# 09_Connectors.net
KiCad netlist of a schematic drawn in Altium Designer
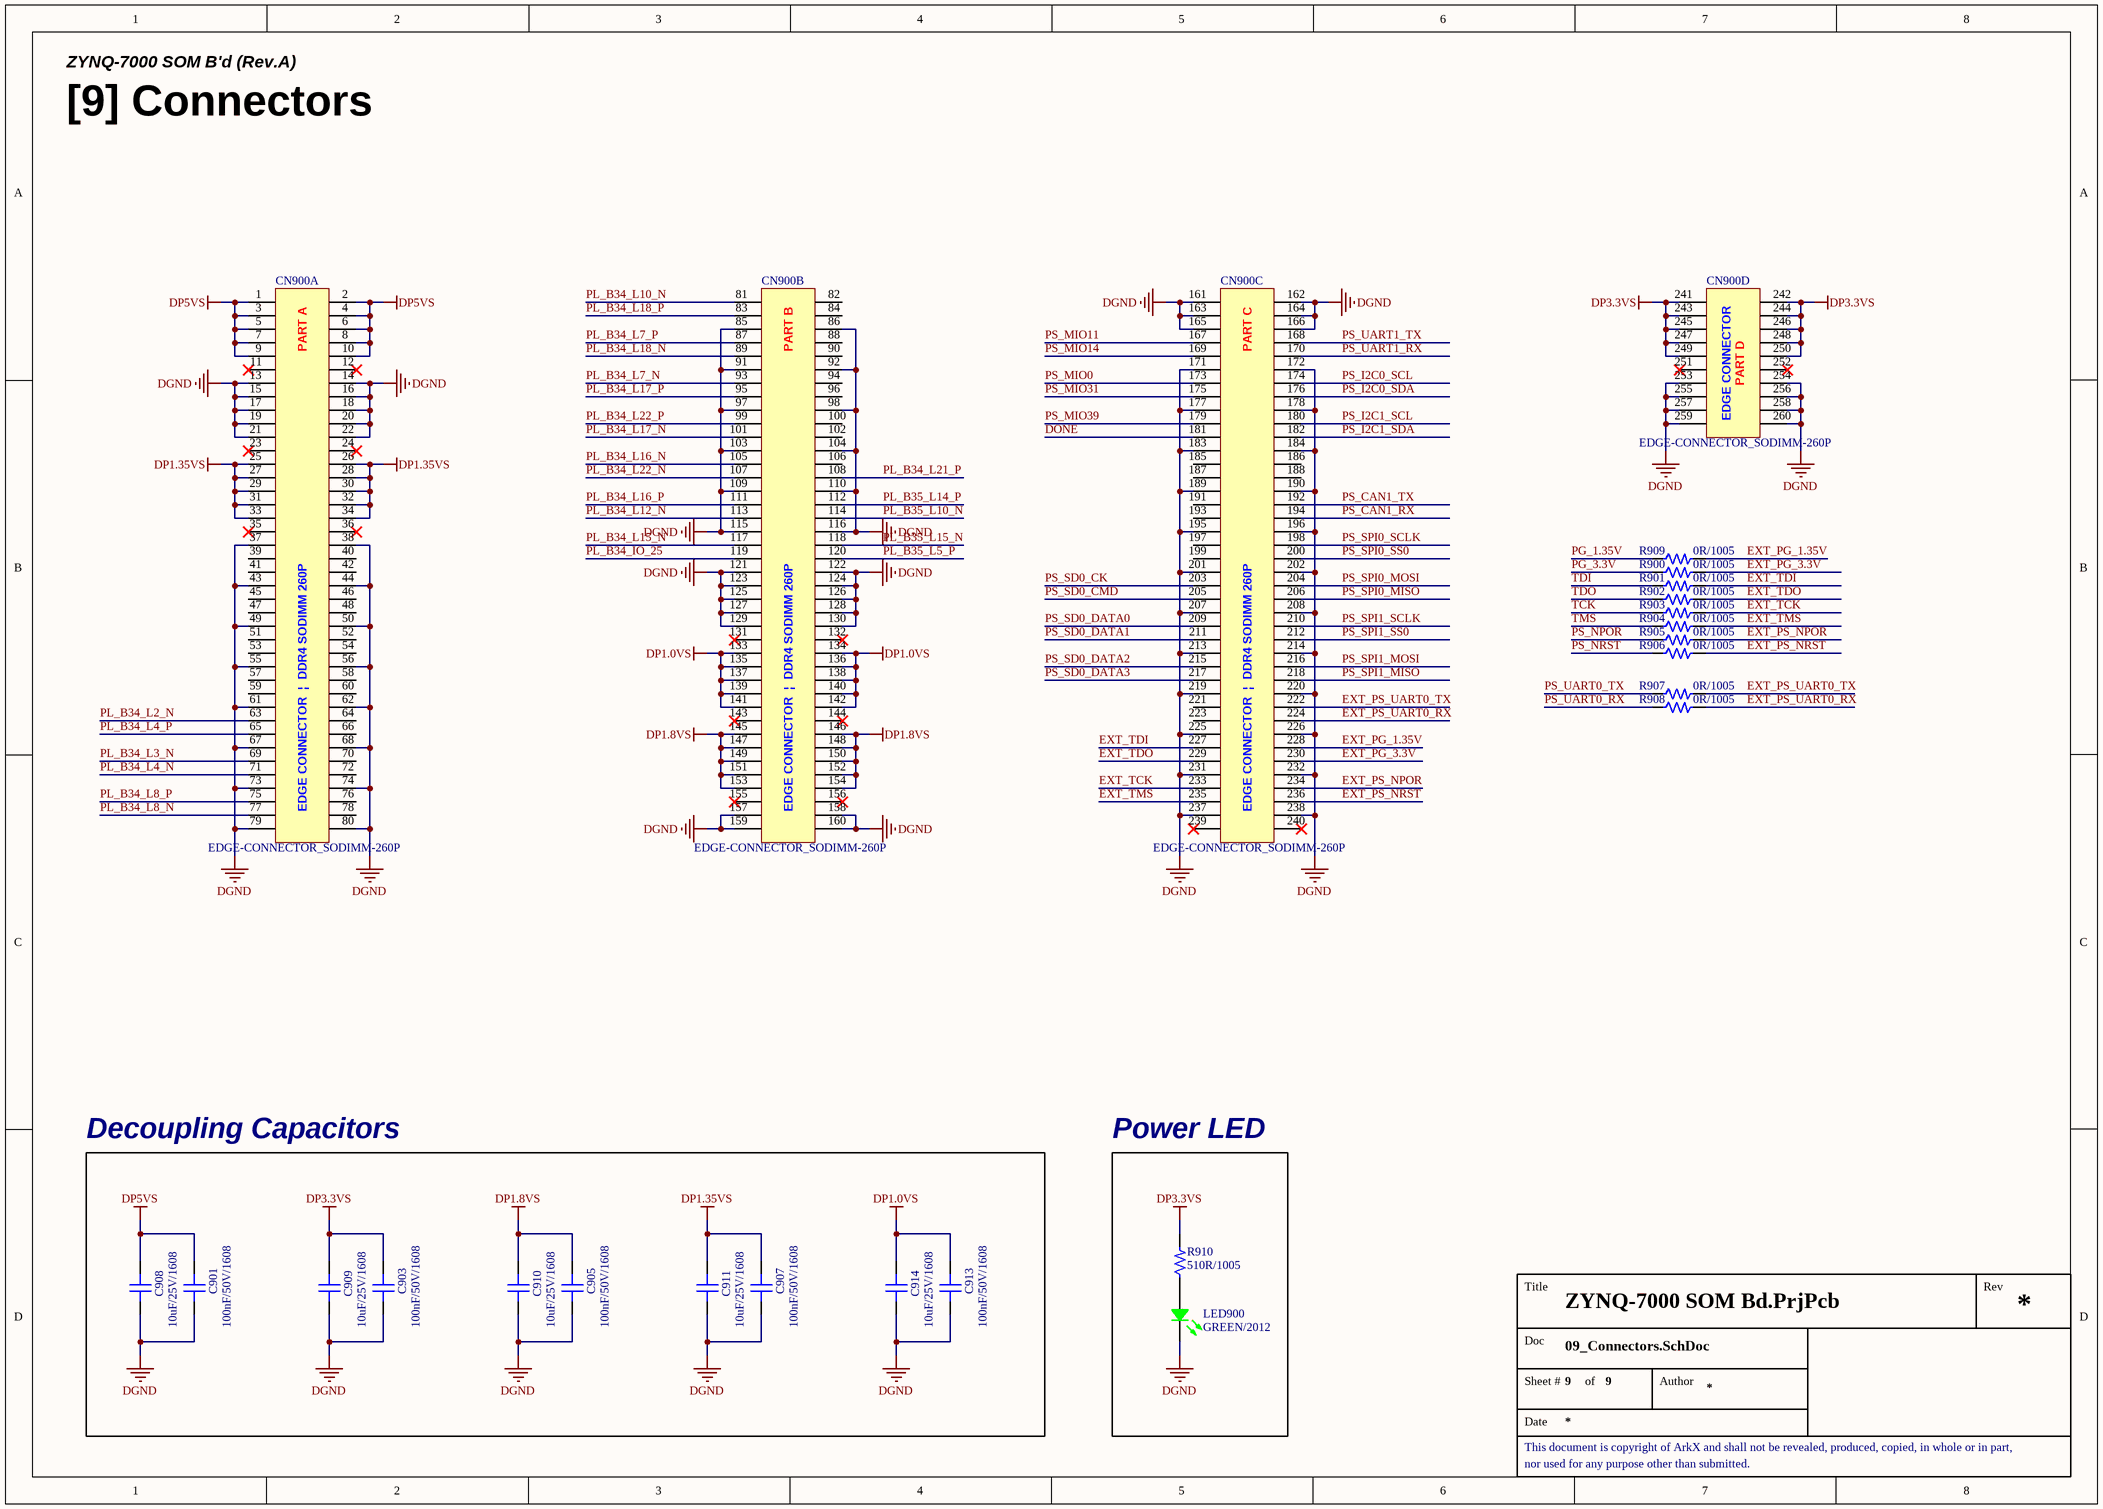
[diagram p0: 09_Connectors.SchDoc]

(export (version "E")
  (design (tool "Eeschema 10.0.6"))
  (components
    (comp (ref "C901")
      (value "100nF/50V/1608")
      (footprint "CAP 1608 (0603_INCH)")
      (description "Ceramic CAP_100nF/50V/1608")
      (fields (field (name "LCSC PART #") "C14663"))
      (libsource (lib "Arkx") (part "CAP_100nF/50V/1608"))
    )
    (comp (ref "C903")
      (value "100nF/50V/1608")
      (footprint "CAP 1608 (0603_INCH)")
      (description "Ceramic CAP_100nF/50V/1608")
      (fields (field (name "LCSC PART #") "C14663"))
      (libsource (lib "Arkx") (part "CAP_100nF/50V/1608"))
    )
    (comp (ref "C905")
      (value "100nF/50V/1608")
      (footprint "CAP 1608 (0603_INCH)")
      (description "Ceramic CAP_100nF/50V/1608")
      (fields (field (name "LCSC PART #") "C14663"))
      (libsource (lib "Arkx") (part "CAP_100nF/50V/1608"))
    )
    (comp (ref "C907")
      (value "100nF/50V/1608")
      (footprint "CAP 1608 (0603_INCH)")
      (description "Ceramic CAP_100nF/50V/1608")
      (fields (field (name "LCSC PART #") "C14663"))
      (libsource (lib "Arkx") (part "CAP_100nF/50V/1608"))
    )
    (comp (ref "C908")
      (value "10uF/25V/1608")
      (footprint "CAP 1608 (0603_INCH)")
      (description "Ceramic CAP_10uF/25V/1608")
      (fields (field (name "LCSC PART #") "C96446"))
      (libsource (lib "Arkx") (part "CAP_10uF/25V/1608"))
    )
    (comp (ref "C909")
      (value "10uF/25V/1608")
      (footprint "CAP 1608 (0603_INCH)")
      (description "Ceramic CAP_10uF/25V/1608")
      (fields (field (name "LCSC PART #") "C96446"))
      (libsource (lib "Arkx") (part "CAP_10uF/25V/1608"))
    )
    (comp (ref "C910")
      (value "10uF/25V/1608")
      (footprint "CAP 1608 (0603_INCH)")
      (description "Ceramic CAP_10uF/25V/1608")
      (fields (field (name "LCSC PART #") "C96446"))
      (libsource (lib "Arkx") (part "CAP_10uF/25V/1608"))
    )
    (comp (ref "C911")
      (value "10uF/25V/1608")
      (footprint "CAP 1608 (0603_INCH)")
      (description "Ceramic CAP_10uF/25V/1608")
      (fields (field (name "LCSC PART #") "C96446"))
      (libsource (lib "Arkx") (part "CAP_10uF/25V/1608"))
    )
    (comp (ref "C913")
      (value "100nF/50V/1608")
      (footprint "CAP 1608 (0603_INCH)")
      (description "Ceramic CAP_100nF/50V/1608")
      (fields (field (name "LCSC PART #") "C14663"))
      (libsource (lib "Arkx") (part "CAP_100nF/50V/1608"))
    )
    (comp (ref "C914")
      (value "10uF/25V/1608")
      (footprint "CAP 1608 (0603_INCH)")
      (description "Ceramic CAP_10uF/25V/1608")
      (fields (field (name "LCSC PART #") "C96446"))
      (libsource (lib "Arkx") (part "CAP_10uF/25V/1608"))
    )
    (comp (ref "CN900")
      (value "EDGE-CONNECTOR_SODIMM-260P")
      (footprint "CON_EDGE-CONNECTOR_DDR4-SODIMM-260P")
      (description "EDGE-CONNECTOR_DDR4-SODIMM-260P")
      (fields (field (name "MATING PART NUMBER") "2309409-1"))
      (libsource (lib "Arkx") (part "CON_EDGE-CONNECTOR_DDR4-SODIMM-260P"))
    )
    (comp (ref "LED900")
      (value "GREEN/2012")
      (footprint "LED MHT170RGBCT (GREEN)")
      (fields (field (name "LCSC PART #") "C2962094"))
      (libsource (lib "Arkx") (part "LED_MHT170RGBCT(GREEN)"))
    )
    (comp (ref "R900")
      (value "0R/1005")
      (footprint "RES 1005 (0402_inch)")
      (description "RES_0R/1005/62.5mW")
      (fields (field (name "LCSC PART #") "C17168"))
      (libsource (lib "Arkx") (part "RES_0R/1005/62.5mW"))
    )
    (comp (ref "R901")
      (value "0R/1005")
      (footprint "RES 1005 (0402_inch)")
      (description "RES_0R/1005/62.5mW")
      (fields (field (name "LCSC PART #") "C17168"))
      (libsource (lib "Arkx") (part "RES_0R/1005/62.5mW"))
    )
    (comp (ref "R902")
      (value "0R/1005")
      (footprint "RES 1005 (0402_inch)")
      (description "RES_0R/1005/62.5mW")
      (fields (field (name "LCSC PART #") "C17168"))
      (libsource (lib "Arkx") (part "RES_0R/1005/62.5mW"))
    )
    (comp (ref "R903")
      (value "0R/1005")
      (footprint "RES 1005 (0402_inch)")
      (description "RES_0R/1005/62.5mW")
      (fields (field (name "LCSC PART #") "C17168"))
      (libsource (lib "Arkx") (part "RES_0R/1005/62.5mW"))
    )
    (comp (ref "R904")
      (value "0R/1005")
      (footprint "RES 1005 (0402_inch)")
      (description "RES_0R/1005/62.5mW")
      (fields (field (name "LCSC PART #") "C17168"))
      (libsource (lib "Arkx") (part "RES_0R/1005/62.5mW"))
    )
    (comp (ref "R905")
      (value "0R/1005")
      (footprint "RES 1005 (0402_inch)")
      (description "RES_0R/1005/62.5mW")
      (fields (field (name "LCSC PART #") "C17168"))
      (libsource (lib "Arkx") (part "RES_0R/1005/62.5mW"))
    )
    (comp (ref "R906")
      (value "0R/1005")
      (footprint "RES 1005 (0402_inch)")
      (description "RES_0R/1005/62.5mW")
      (fields (field (name "LCSC PART #") "C17168"))
      (libsource (lib "Arkx") (part "RES_0R/1005/62.5mW"))
    )
    (comp (ref "R907")
      (value "0R/1005")
      (footprint "RES 1005 (0402_inch)")
      (description "RES_0R/1005/62.5mW")
      (fields (field (name "LCSC PART #") "C17168"))
      (libsource (lib "Arkx") (part "RES_0R/1005/62.5mW"))
    )
    (comp (ref "R908")
      (value "0R/1005")
      (footprint "RES 1005 (0402_inch)")
      (description "RES_0R/1005/62.5mW")
      (fields (field (name "LCSC PART #") "C17168"))
      (libsource (lib "Arkx") (part "RES_0R/1005/62.5mW"))
    )
    (comp (ref "R909")
      (value "0R/1005")
      (footprint "RES 1005 (0402_inch)")
      (description "RES_0R/1005/62.5mW")
      (fields (field (name "LCSC PART #") "C17168"))
      (libsource (lib "Arkx") (part "RES_0R/1005/62.5mW"))
    )
    (comp (ref "R910")
      (value "510R/1005")
      (footprint "RES 1005 (0402_inch)")
      (description "RES_510R/1005/62.5mW")
      (fields (field (name "LCSC PART #") "C25123"))
      (libsource (lib "Arkx") (part "RES_510R/1005/62.5mW"))
    )
  )
  (nets
    (net (code "1") (name "/DONE") (class "Default")
      (node (ref "CN900") (pin "181") (pinfunction "181_181") (pintype "passive"))
    )
    (net (code "2") (name "/EXT_PG_1.35V") (class "Default")
      (node (ref "CN900") (pin "228") (pinfunction "228_228") (pintype "passive"))
      (node (ref "R909") (pin "2") (pinfunction "2_2") (pintype "passive"))
    )
    (net (code "3") (name "/EXT_PG_3.3V") (class "Default")
      (node (ref "CN900") (pin "230") (pinfunction "230_230") (pintype "passive"))
      (node (ref "R900") (pin "2") (pinfunction "2_2") (pintype "passive"))
    )
    (net (code "4") (name "/EXT_PS_NPOR") (class "Default")
      (node (ref "CN900") (pin "234") (pinfunction "234_234") (pintype "passive"))
      (node (ref "R905") (pin "2") (pinfunction "2_2") (pintype "passive"))
    )
    (net (code "5") (name "/EXT_PS_NRST") (class "Default")
      (node (ref "CN900") (pin "236") (pinfunction "236_236") (pintype "passive"))
      (node (ref "R906") (pin "2") (pinfunction "2_2") (pintype "passive"))
    )
    (net (code "6") (name "/EXT_PS_UART0_RX") (class "Default")
      (node (ref "CN900") (pin "224") (pinfunction "224_224") (pintype "passive"))
      (node (ref "R908") (pin "2") (pinfunction "2_2") (pintype "passive"))
    )
    (net (code "7") (name "/EXT_PS_UART0_TX") (class "Default")
      (node (ref "CN900") (pin "222") (pinfunction "222_222") (pintype "passive"))
      (node (ref "R907") (pin "2") (pinfunction "2_2") (pintype "passive"))
    )
    (net (code "8") (name "/EXT_TCK") (class "Default")
      (node (ref "CN900") (pin "233") (pinfunction "233_233") (pintype "passive"))
      (node (ref "R903") (pin "2") (pinfunction "2_2") (pintype "passive"))
    )
    (net (code "9") (name "/EXT_TDI") (class "Default")
      (node (ref "CN900") (pin "227") (pinfunction "227_227") (pintype "passive"))
      (node (ref "R901") (pin "2") (pinfunction "2_2") (pintype "passive"))
    )
    (net (code "10") (name "/EXT_TDO") (class "Default")
      (node (ref "CN900") (pin "229") (pinfunction "229_229") (pintype "passive"))
      (node (ref "R902") (pin "2") (pinfunction "2_2") (pintype "passive"))
    )
    (net (code "11") (name "/EXT_TMS") (class "Default")
      (node (ref "CN900") (pin "235") (pinfunction "235_235") (pintype "passive"))
      (node (ref "R904") (pin "2") (pinfunction "2_2") (pintype "passive"))
    )
    (net (code "12") (name "/PG_1.35V") (class "Default")
      (node (ref "R909") (pin "1") (pinfunction "1_1") (pintype "passive"))
    )
    (net (code "13") (name "/PG_3.3V") (class "Default")
      (node (ref "R900") (pin "1") (pinfunction "1_1") (pintype "passive"))
    )
    (net (code "14") (name "/PL_B34_IO_25") (class "Default")
      (node (ref "CN900") (pin "119") (pinfunction "119_119") (pintype "passive"))
    )
    (net (code "15") (name "/PL_B34_L2_N") (class "Default")
      (node (ref "CN900") (pin "63") (pinfunction "63_63") (pintype "passive"))
    )
    (net (code "16") (name "/PL_B34_L3_N") (class "Default")
      (node (ref "CN900") (pin "69") (pinfunction "69_69") (pintype "passive"))
    )
    (net (code "17") (name "/PL_B34_L4_N") (class "Default")
      (node (ref "CN900") (pin "71") (pinfunction "71_71") (pintype "passive"))
    )
    (net (code "18") (name "/PL_B34_L4_P") (class "Default")
      (node (ref "CN900") (pin "65") (pinfunction "65_65") (pintype "passive"))
    )
    (net (code "19") (name "/PL_B34_L7_N") (class "Default")
      (node (ref "CN900") (pin "93") (pinfunction "93_93") (pintype "passive"))
    )
    (net (code "20") (name "/PL_B34_L7_P") (class "Default")
      (node (ref "CN900") (pin "87") (pinfunction "87_87") (pintype "passive"))
    )
    (net (code "21") (name "/PL_B34_L8_N") (class "Default")
      (node (ref "CN900") (pin "77") (pinfunction "77_77") (pintype "passive"))
    )
    (net (code "22") (name "/PL_B34_L8_P") (class "Default")
      (node (ref "CN900") (pin "75") (pinfunction "75_75") (pintype "passive"))
    )
    (net (code "23") (name "/PL_B34_L10_N") (class "Default")
      (node (ref "CN900") (pin "81") (pinfunction "81_81") (pintype "passive"))
    )
    (net (code "24") (name "/PL_B34_L12_N") (class "Default")
      (node (ref "CN900") (pin "113") (pinfunction "113_113") (pintype "passive"))
    )
    (net (code "25") (name "/PL_B34_L15_N") (class "Default")
      (node (ref "CN900") (pin "117") (pinfunction "117_117") (pintype "passive"))
    )
    (net (code "26") (name "/PL_B34_L16_N") (class "Default")
      (node (ref "CN900") (pin "105") (pinfunction "105_105") (pintype "passive"))
    )
    (net (code "27") (name "/PL_B34_L16_P") (class "Default")
      (node (ref "CN900") (pin "111") (pinfunction "111_111") (pintype "passive"))
    )
    (net (code "28") (name "/PL_B34_L17_N") (class "Default")
      (node (ref "CN900") (pin "101") (pinfunction "101_101") (pintype "passive"))
    )
    (net (code "29") (name "/PL_B34_L17_P") (class "Default")
      (node (ref "CN900") (pin "95") (pinfunction "95_95") (pintype "passive"))
    )
    (net (code "30") (name "/PL_B34_L18_N") (class "Default")
      (node (ref "CN900") (pin "89") (pinfunction "89_89") (pintype "passive"))
    )
    (net (code "31") (name "/PL_B34_L18_P") (class "Default")
      (node (ref "CN900") (pin "83") (pinfunction "83_83") (pintype "passive"))
    )
    (net (code "32") (name "/PL_B34_L21_P") (class "Default")
      (node (ref "CN900") (pin "108") (pinfunction "108_108") (pintype "passive"))
    )
    (net (code "33") (name "/PL_B34_L22_N") (class "Default")
      (node (ref "CN900") (pin "107") (pinfunction "107_107") (pintype "passive"))
    )
    (net (code "34") (name "/PL_B34_L22_P") (class "Default")
      (node (ref "CN900") (pin "99") (pinfunction "99_99") (pintype "passive"))
    )
    (net (code "35") (name "/PL_B35_L5_P") (class "Default")
      (node (ref "CN900") (pin "120") (pinfunction "120_120") (pintype "passive"))
    )
    (net (code "36") (name "/PL_B35_L10_N") (class "Default")
      (node (ref "CN900") (pin "114") (pinfunction "114_114") (pintype "passive"))
    )
    (net (code "37") (name "/PL_B35_L14_P") (class "Default")
      (node (ref "CN900") (pin "112") (pinfunction "112_112") (pintype "passive"))
    )
    (net (code "38") (name "/PL_B35_L15_N") (class "Default")
      (node (ref "CN900") (pin "118") (pinfunction "118_118") (pintype "passive"))
    )
    (net (code "39") (name "/PS_CAN1_RX") (class "Default")
      (node (ref "CN900") (pin "194") (pinfunction "194_194") (pintype "passive"))
    )
    (net (code "40") (name "/PS_CAN1_TX") (class "Default")
      (node (ref "CN900") (pin "192") (pinfunction "192_192") (pintype "passive"))
    )
    (net (code "41") (name "/PS_I2C0_SCL") (class "Default")
      (node (ref "CN900") (pin "174") (pinfunction "174_174") (pintype "passive"))
    )
    (net (code "42") (name "/PS_I2C0_SDA") (class "Default")
      (node (ref "CN900") (pin "176") (pinfunction "176_176") (pintype "passive"))
    )
    (net (code "43") (name "/PS_I2C1_SCL") (class "Default")
      (node (ref "CN900") (pin "180") (pinfunction "180_180") (pintype "passive"))
    )
    (net (code "44") (name "/PS_I2C1_SDA") (class "Default")
      (node (ref "CN900") (pin "182") (pinfunction "182_182") (pintype "passive"))
    )
    (net (code "45") (name "/PS_MIO0") (class "Default")
      (node (ref "CN900") (pin "173") (pinfunction "173_173") (pintype "passive"))
    )
    (net (code "46") (name "/PS_MIO11") (class "Default")
      (node (ref "CN900") (pin "167") (pinfunction "167_167") (pintype "passive"))
    )
    (net (code "47") (name "/PS_MIO14") (class "Default")
      (node (ref "CN900") (pin "169") (pinfunction "169_169") (pintype "passive"))
    )
    (net (code "48") (name "/PS_MIO31") (class "Default")
      (node (ref "CN900") (pin "175") (pinfunction "175_175") (pintype "passive"))
    )
    (net (code "49") (name "/PS_MIO39") (class "Default")
      (node (ref "CN900") (pin "179") (pinfunction "179_179") (pintype "passive"))
    )
    (net (code "50") (name "/PS_NPOR") (class "Default")
      (node (ref "R905") (pin "1") (pinfunction "1_1") (pintype "passive"))
    )
    (net (code "51") (name "/PS_NRST") (class "Default")
      (node (ref "R906") (pin "1") (pinfunction "1_1") (pintype "passive"))
    )
    (net (code "52") (name "/PS_SD0_CK") (class "Default")
      (node (ref "CN900") (pin "203") (pinfunction "203_203") (pintype "passive"))
    )
    (net (code "53") (name "/PS_SD0_CMD") (class "Default")
      (node (ref "CN900") (pin "205") (pinfunction "205_205") (pintype "passive"))
    )
    (net (code "54") (name "/PS_SD0_DATA0") (class "Default")
      (node (ref "CN900") (pin "209") (pinfunction "209_209") (pintype "passive"))
    )
    (net (code "55") (name "/PS_SD0_DATA1") (class "Default")
      (node (ref "CN900") (pin "211") (pinfunction "211_211") (pintype "passive"))
    )
    (net (code "56") (name "/PS_SD0_DATA2") (class "Default")
      (node (ref "CN900") (pin "215") (pinfunction "215_215") (pintype "passive"))
    )
    (net (code "57") (name "/PS_SD0_DATA3") (class "Default")
      (node (ref "CN900") (pin "217") (pinfunction "217_217") (pintype "passive"))
    )
    (net (code "58") (name "/PS_SPI0_MISO") (class "Default")
      (node (ref "CN900") (pin "206") (pinfunction "206_206") (pintype "passive"))
    )
    (net (code "59") (name "/PS_SPI0_MOSI") (class "Default")
      (node (ref "CN900") (pin "204") (pinfunction "204_204") (pintype "passive"))
    )
    (net (code "60") (name "/PS_SPI0_SCLK") (class "Default")
      (node (ref "CN900") (pin "198") (pinfunction "198_198") (pintype "passive"))
    )
    (net (code "61") (name "/PS_SPI0_SS0") (class "Default")
      (node (ref "CN900") (pin "200") (pinfunction "200_200") (pintype "passive"))
    )
    (net (code "62") (name "/PS_SPI1_MISO") (class "Default")
      (node (ref "CN900") (pin "218") (pinfunction "218_218") (pintype "passive"))
    )
    (net (code "63") (name "/PS_SPI1_MOSI") (class "Default")
      (node (ref "CN900") (pin "216") (pinfunction "216_216") (pintype "passive"))
    )
    (net (code "64") (name "/PS_SPI1_SCLK") (class "Default")
      (node (ref "CN900") (pin "210") (pinfunction "210_210") (pintype "passive"))
    )
    (net (code "65") (name "/PS_SPI1_SS0") (class "Default")
      (node (ref "CN900") (pin "212") (pinfunction "212_212") (pintype "passive"))
    )
    (net (code "66") (name "/PS_UART0_RX") (class "Default")
      (node (ref "R908") (pin "1") (pinfunction "1_1") (pintype "passive"))
    )
    (net (code "67") (name "/PS_UART0_TX") (class "Default")
      (node (ref "R907") (pin "1") (pinfunction "1_1") (pintype "passive"))
    )
    (net (code "68") (name "/PS_UART1_RX") (class "Default")
      (node (ref "CN900") (pin "170") (pinfunction "170_170") (pintype "passive"))
    )
    (net (code "69") (name "/PS_UART1_TX") (class "Default")
      (node (ref "CN900") (pin "168") (pinfunction "168_168") (pintype "passive"))
    )
    (net (code "70") (name "/TCK") (class "Default")
      (node (ref "R903") (pin "1") (pinfunction "1_1") (pintype "passive"))
    )
    (net (code "71") (name "/TDI") (class "Default")
      (node (ref "R901") (pin "1") (pinfunction "1_1") (pintype "passive"))
    )
    (net (code "72") (name "/TDO") (class "Default")
      (node (ref "R902") (pin "1") (pinfunction "1_1") (pintype "passive"))
    )
    (net (code "73") (name "/TMS") (class "Default")
      (node (ref "R904") (pin "1") (pinfunction "1_1") (pintype "passive"))
    )
    (net (code "74") (name "DGND") (class "Default")
      (node (ref "C901") (pin "1") (pinfunction "1_1") (pintype "passive"))
      (node (ref "C903") (pin "1") (pinfunction "1_1") (pintype "passive"))
      (node (ref "C905") (pin "1") (pinfunction "1_1") (pintype "passive"))
      (node (ref "C907") (pin "1") (pinfunction "1_1") (pintype "passive"))
      (node (ref "C908") (pin "1") (pinfunction "1_1") (pintype "passive"))
      (node (ref "C909") (pin "1") (pinfunction "1_1") (pintype "passive"))
      (node (ref "C910") (pin "1") (pinfunction "1_1") (pintype "passive"))
      (node (ref "C911") (pin "1") (pinfunction "1_1") (pintype "passive"))
      (node (ref "C913") (pin "1") (pinfunction "1_1") (pintype "passive"))
      (node (ref "C914") (pin "1") (pinfunction "1_1") (pintype "passive"))
      (node (ref "CN900") (pin "103") (pinfunction "103_103") (pintype "passive"))
      (node (ref "CN900") (pin "104") (pinfunction "104_104") (pintype "passive"))
      (node (ref "CN900") (pin "109") (pinfunction "109_109") (pintype "passive"))
      (node (ref "CN900") (pin "110") (pinfunction "110_110") (pintype "passive"))
      (node (ref "CN900") (pin "115") (pinfunction "115_115") (pintype "passive"))
      (node (ref "CN900") (pin "116") (pinfunction "116_116") (pintype "passive"))
      (node (ref "CN900") (pin "121") (pinfunction "121_121") (pintype "passive"))
      (node (ref "CN900") (pin "122") (pinfunction "122_122") (pintype "passive"))
      (node (ref "CN900") (pin "123") (pinfunction "123_123") (pintype "passive"))
      (node (ref "CN900") (pin "124") (pinfunction "124_124") (pintype "passive"))
      (node (ref "CN900") (pin "125") (pinfunction "125_125") (pintype "passive"))
      (node (ref "CN900") (pin "126") (pinfunction "126_126") (pintype "passive"))
      (node (ref "CN900") (pin "127") (pinfunction "127_127") (pintype "passive"))
      (node (ref "CN900") (pin "128") (pinfunction "128_128") (pintype "passive"))
      (node (ref "CN900") (pin "129") (pinfunction "129_129") (pintype "passive"))
      (node (ref "CN900") (pin "13") (pinfunction "13_13") (pintype "passive"))
      (node (ref "CN900") (pin "130") (pinfunction "130_130") (pintype "passive"))
      (node (ref "CN900") (pin "14") (pinfunction "14_14") (pintype "passive"))
      (node (ref "CN900") (pin "15") (pinfunction "15_15") (pintype "passive"))
      (node (ref "CN900") (pin "157") (pinfunction "157_157") (pintype "passive"))
      (node (ref "CN900") (pin "158") (pinfunction "158_158") (pintype "passive"))
      (node (ref "CN900") (pin "159") (pinfunction "159_159") (pintype "passive"))
      (node (ref "CN900") (pin "16") (pinfunction "16_16") (pintype "passive"))
      (node (ref "CN900") (pin "160") (pinfunction "160_160") (pintype "passive"))
      (node (ref "CN900") (pin "161") (pinfunction "161_161") (pintype "passive"))
      (node (ref "CN900") (pin "162") (pinfunction "162_162") (pintype "passive"))
      (node (ref "CN900") (pin "163") (pinfunction "163_163") (pintype "passive"))
      (node (ref "CN900") (pin "164") (pinfunction "164_164") (pintype "passive"))
      (node (ref "CN900") (pin "165") (pinfunction "165_165") (pintype "passive"))
      (node (ref "CN900") (pin "166") (pinfunction "166_166") (pintype "passive"))
      (node (ref "CN900") (pin "17") (pinfunction "17_17") (pintype "passive"))
      (node (ref "CN900") (pin "171") (pinfunction "171_171") (pintype "passive"))
      (node (ref "CN900") (pin "172") (pinfunction "172_172") (pintype "passive"))
      (node (ref "CN900") (pin "177") (pinfunction "177_177") (pintype "passive"))
      (node (ref "CN900") (pin "178") (pinfunction "178_178") (pintype "passive"))
      (node (ref "CN900") (pin "18") (pinfunction "18_18") (pintype "passive"))
      (node (ref "CN900") (pin "183") (pinfunction "183_183") (pintype "passive"))
      (node (ref "CN900") (pin "184") (pinfunction "184_184") (pintype "passive"))
      (node (ref "CN900") (pin "189") (pinfunction "189_189") (pintype "passive"))
      (node (ref "CN900") (pin "19") (pinfunction "19_19") (pintype "passive"))
      (node (ref "CN900") (pin "190") (pinfunction "190_190") (pintype "passive"))
      (node (ref "CN900") (pin "195") (pinfunction "195_195") (pintype "passive"))
      (node (ref "CN900") (pin "196") (pinfunction "196_196") (pintype "passive"))
      (node (ref "CN900") (pin "20") (pinfunction "20_20") (pintype "passive"))
      (node (ref "CN900") (pin "201") (pinfunction "201_201") (pintype "passive"))
      (node (ref "CN900") (pin "202") (pinfunction "202_202") (pintype "passive"))
      (node (ref "CN900") (pin "207") (pinfunction "207_207") (pintype "passive"))
      (node (ref "CN900") (pin "208") (pinfunction "208_208") (pintype "passive"))
      (node (ref "CN900") (pin "21") (pinfunction "21_21") (pintype "passive"))
      (node (ref "CN900") (pin "213") (pinfunction "213_213") (pintype "passive"))
      (node (ref "CN900") (pin "214") (pinfunction "214_214") (pintype "passive"))
      (node (ref "CN900") (pin "219") (pinfunction "219_219") (pintype "passive"))
      (node (ref "CN900") (pin "22") (pinfunction "22_22") (pintype "passive"))
      (node (ref "CN900") (pin "220") (pinfunction "220_220") (pintype "passive"))
      (node (ref "CN900") (pin "225") (pinfunction "225_225") (pintype "passive"))
      (node (ref "CN900") (pin "226") (pinfunction "226_226") (pintype "passive"))
      (node (ref "CN900") (pin "231") (pinfunction "231_231") (pintype "passive"))
      (node (ref "CN900") (pin "232") (pinfunction "232_232") (pintype "passive"))
      (node (ref "CN900") (pin "237") (pinfunction "237_237") (pintype "passive"))
      (node (ref "CN900") (pin "238") (pinfunction "238_238") (pintype "passive"))
      (node (ref "CN900") (pin "253") (pinfunction "253_253") (pintype "passive"))
      (node (ref "CN900") (pin "254") (pinfunction "254_254") (pintype "passive"))
      (node (ref "CN900") (pin "255") (pinfunction "255_255") (pintype "passive"))
      (node (ref "CN900") (pin "256") (pinfunction "256_256") (pintype "passive"))
      (node (ref "CN900") (pin "257") (pinfunction "257_257") (pintype "passive"))
      (node (ref "CN900") (pin "258") (pinfunction "258_258") (pintype "passive"))
      (node (ref "CN900") (pin "259") (pinfunction "259_259") (pintype "passive"))
      (node (ref "CN900") (pin "260") (pinfunction "260_260") (pintype "passive"))
      (node (ref "CN900") (pin "37") (pinfunction "37_37") (pintype "passive"))
      (node (ref "CN900") (pin "38") (pinfunction "38_38") (pintype "passive"))
      (node (ref "CN900") (pin "43") (pinfunction "43_43") (pintype "passive"))
      (node (ref "CN900") (pin "44") (pinfunction "44_44") (pintype "passive"))
      (node (ref "CN900") (pin "49") (pinfunction "49_49") (pintype "passive"))
      (node (ref "CN900") (pin "50") (pinfunction "50_50") (pintype "passive"))
      (node (ref "CN900") (pin "55") (pinfunction "55_55") (pintype "passive"))
      (node (ref "CN900") (pin "56") (pinfunction "56_56") (pintype "passive"))
      (node (ref "CN900") (pin "61") (pinfunction "61_61") (pintype "passive"))
      (node (ref "CN900") (pin "62") (pinfunction "62_62") (pintype "passive"))
      (node (ref "CN900") (pin "67") (pinfunction "67_67") (pintype "passive"))
      (node (ref "CN900") (pin "68") (pinfunction "68_68") (pintype "passive"))
      (node (ref "CN900") (pin "73") (pinfunction "73_73") (pintype "passive"))
      (node (ref "CN900") (pin "74") (pinfunction "74_74") (pintype "passive"))
      (node (ref "CN900") (pin "79") (pinfunction "79_79") (pintype "passive"))
      (node (ref "CN900") (pin "80") (pinfunction "80_80") (pintype "passive"))
      (node (ref "CN900") (pin "85") (pinfunction "85_85") (pintype "passive"))
      (node (ref "CN900") (pin "86") (pinfunction "86_86") (pintype "passive"))
      (node (ref "CN900") (pin "91") (pinfunction "91_91") (pintype "passive"))
      (node (ref "CN900") (pin "92") (pinfunction "92_92") (pintype "passive"))
      (node (ref "CN900") (pin "97") (pinfunction "97_97") (pintype "passive"))
      (node (ref "CN900") (pin "98") (pinfunction "98_98") (pintype "passive"))
      (node (ref "LED900") (pin "2") (pinfunction "GREEN_2") (pintype "passive"))
    )
    (net (code "75") (name "DP1.0VS") (class "Default")
      (node (ref "C913") (pin "2") (pinfunction "2_2") (pintype "passive"))
      (node (ref "C914") (pin "2") (pinfunction "2_2") (pintype "passive"))
      (node (ref "CN900") (pin "133") (pinfunction "133_133") (pintype "passive"))
      (node (ref "CN900") (pin "134") (pinfunction "134_134") (pintype "passive"))
      (node (ref "CN900") (pin "135") (pinfunction "135_135") (pintype "passive"))
      (node (ref "CN900") (pin "136") (pinfunction "136_136") (pintype "passive"))
      (node (ref "CN900") (pin "137") (pinfunction "137_137") (pintype "passive"))
      (node (ref "CN900") (pin "138") (pinfunction "138_138") (pintype "passive"))
      (node (ref "CN900") (pin "139") (pinfunction "139_139") (pintype "passive"))
      (node (ref "CN900") (pin "140") (pinfunction "140_140") (pintype "passive"))
      (node (ref "CN900") (pin "141") (pinfunction "141_141") (pintype "passive"))
      (node (ref "CN900") (pin "142") (pinfunction "142_142") (pintype "passive"))
    )
    (net (code "76") (name "DP1.8VS") (class "Default")
      (node (ref "C905") (pin "2") (pinfunction "2_2") (pintype "passive"))
      (node (ref "C910") (pin "2") (pinfunction "2_2") (pintype "passive"))
      (node (ref "CN900") (pin "145") (pinfunction "145_145") (pintype "passive"))
      (node (ref "CN900") (pin "146") (pinfunction "146_146") (pintype "passive"))
      (node (ref "CN900") (pin "147") (pinfunction "147_147") (pintype "passive"))
      (node (ref "CN900") (pin "148") (pinfunction "148_148") (pintype "passive"))
      (node (ref "CN900") (pin "149") (pinfunction "149_149") (pintype "passive"))
      (node (ref "CN900") (pin "150") (pinfunction "150_150") (pintype "passive"))
      (node (ref "CN900") (pin "151") (pinfunction "151_151") (pintype "passive"))
      (node (ref "CN900") (pin "152") (pinfunction "152_152") (pintype "passive"))
      (node (ref "CN900") (pin "153") (pinfunction "153_153") (pintype "passive"))
      (node (ref "CN900") (pin "154") (pinfunction "154_154") (pintype "passive"))
    )
    (net (code "77") (name "DP1.35VS") (class "Default")
      (node (ref "C907") (pin "2") (pinfunction "2_2") (pintype "passive"))
      (node (ref "C911") (pin "2") (pinfunction "2_2") (pintype "passive"))
      (node (ref "CN900") (pin "25") (pinfunction "25_25") (pintype "passive"))
      (node (ref "CN900") (pin "26") (pinfunction "26_26") (pintype "passive"))
      (node (ref "CN900") (pin "27") (pinfunction "27_27") (pintype "passive"))
      (node (ref "CN900") (pin "28") (pinfunction "28_28") (pintype "passive"))
      (node (ref "CN900") (pin "29") (pinfunction "29_29") (pintype "passive"))
      (node (ref "CN900") (pin "30") (pinfunction "30_30") (pintype "passive"))
      (node (ref "CN900") (pin "31") (pinfunction "31_31") (pintype "passive"))
      (node (ref "CN900") (pin "32") (pinfunction "32_32") (pintype "passive"))
      (node (ref "CN900") (pin "33") (pinfunction "33_33") (pintype "passive"))
      (node (ref "CN900") (pin "34") (pinfunction "34_34") (pintype "passive"))
    )
    (net (code "78") (name "DP3.3VS") (class "Default")
      (node (ref "C903") (pin "2") (pinfunction "2_2") (pintype "passive"))
      (node (ref "C909") (pin "2") (pinfunction "2_2") (pintype "passive"))
      (node (ref "CN900") (pin "241") (pinfunction "241_241") (pintype "passive"))
      (node (ref "CN900") (pin "242") (pinfunction "242_242") (pintype "passive"))
      (node (ref "CN900") (pin "243") (pinfunction "243_243") (pintype "passive"))
      (node (ref "CN900") (pin "244") (pinfunction "244_244") (pintype "passive"))
      (node (ref "CN900") (pin "245") (pinfunction "245_245") (pintype "passive"))
      (node (ref "CN900") (pin "246") (pinfunction "246_246") (pintype "passive"))
      (node (ref "CN900") (pin "247") (pinfunction "247_247") (pintype "passive"))
      (node (ref "CN900") (pin "248") (pinfunction "248_248") (pintype "passive"))
      (node (ref "CN900") (pin "249") (pinfunction "249_249") (pintype "passive"))
      (node (ref "CN900") (pin "250") (pinfunction "250_250") (pintype "passive"))
      (node (ref "R910") (pin "2") (pinfunction "2_2") (pintype "passive"))
    )
    (net (code "79") (name "DP5VS") (class "Default")
      (node (ref "C901") (pin "2") (pinfunction "2_2") (pintype "passive"))
      (node (ref "C908") (pin "2") (pinfunction "2_2") (pintype "passive"))
      (node (ref "CN900") (pin "1") (pinfunction "1_1") (pintype "passive"))
      (node (ref "CN900") (pin "10") (pinfunction "10_10") (pintype "passive"))
      (node (ref "CN900") (pin "2") (pinfunction "2_2") (pintype "passive"))
      (node (ref "CN900") (pin "3") (pinfunction "3_3") (pintype "passive"))
      (node (ref "CN900") (pin "4") (pinfunction "4_4") (pintype "passive"))
      (node (ref "CN900") (pin "5") (pinfunction "5_5") (pintype "passive"))
      (node (ref "CN900") (pin "6") (pinfunction "6_6") (pintype "passive"))
      (node (ref "CN900") (pin "7") (pinfunction "7_7") (pintype "passive"))
      (node (ref "CN900") (pin "8") (pinfunction "8_8") (pintype "passive"))
      (node (ref "CN900") (pin "9") (pinfunction "9_9") (pintype "passive"))
    )
    (net (code "80") (name "Net-(LED900-Common_Anode)") (class "Default")
      (node (ref "LED900") (pin "4") (pinfunction "Common_Anode_4") (pintype "passive"))
      (node (ref "R910") (pin "1") (pinfunction "1_1") (pintype "passive"))
    )
    (net (code "81") (name "unconnected-(CN900-Pad11)") (class "Default")
      (node (ref "CN900") (pin "11") (pinfunction "11_11") (pintype "passive+no_connect"))
    )
    (net (code "82") (name "unconnected-(CN900-Pad12)") (class "Default")
      (node (ref "CN900") (pin "12") (pinfunction "12_12") (pintype "passive+no_connect"))
    )
    (net (code "83") (name "unconnected-(CN900-Pad23)") (class "Default")
      (node (ref "CN900") (pin "23") (pinfunction "23_23") (pintype "passive+no_connect"))
    )
    (net (code "84") (name "unconnected-(CN900-Pad24)") (class "Default")
      (node (ref "CN900") (pin "24") (pinfunction "24_24") (pintype "passive+no_connect"))
    )
    (net (code "85") (name "unconnected-(CN900-Pad35)") (class "Default")
      (node (ref "CN900") (pin "35") (pinfunction "35_35") (pintype "passive+no_connect"))
    )
    (net (code "86") (name "unconnected-(CN900-Pad36)") (class "Default")
      (node (ref "CN900") (pin "36") (pinfunction "36_36") (pintype "passive+no_connect"))
    )
    (net (code "87") (name "unconnected-(CN900-Pad39)") (class "Default")
      (node (ref "CN900") (pin "39") (pinfunction "39_39") (pintype "passive"))
    )
    (net (code "88") (name "unconnected-(CN900-Pad40)") (class "Default")
      (node (ref "CN900") (pin "40") (pinfunction "40_40") (pintype "passive"))
    )
    (net (code "89") (name "unconnected-(CN900-Pad41)") (class "Default")
      (node (ref "CN900") (pin "41") (pinfunction "41_41") (pintype "passive"))
    )
    (net (code "90") (name "unconnected-(CN900-Pad42)") (class "Default")
      (node (ref "CN900") (pin "42") (pinfunction "42_42") (pintype "passive"))
    )
    (net (code "91") (name "unconnected-(CN900-Pad45)") (class "Default")
      (node (ref "CN900") (pin "45") (pinfunction "45_45") (pintype "passive"))
    )
    (net (code "92") (name "unconnected-(CN900-Pad46)") (class "Default")
      (node (ref "CN900") (pin "46") (pinfunction "46_46") (pintype "passive"))
    )
    (net (code "93") (name "unconnected-(CN900-Pad47)") (class "Default")
      (node (ref "CN900") (pin "47") (pinfunction "47_47") (pintype "passive"))
    )
    (net (code "94") (name "unconnected-(CN900-Pad48)") (class "Default")
      (node (ref "CN900") (pin "48") (pinfunction "48_48") (pintype "passive"))
    )
    (net (code "95") (name "unconnected-(CN900-Pad51)") (class "Default")
      (node (ref "CN900") (pin "51") (pinfunction "51_51") (pintype "passive"))
    )
    (net (code "96") (name "unconnected-(CN900-Pad52)") (class "Default")
      (node (ref "CN900") (pin "52") (pinfunction "52_52") (pintype "passive"))
    )
    (net (code "97") (name "unconnected-(CN900-Pad53)") (class "Default")
      (node (ref "CN900") (pin "53") (pinfunction "53_53") (pintype "passive"))
    )
    (net (code "98") (name "unconnected-(CN900-Pad54)") (class "Default")
      (node (ref "CN900") (pin "54") (pinfunction "54_54") (pintype "passive"))
    )
    (net (code "99") (name "unconnected-(CN900-Pad57)") (class "Default")
      (node (ref "CN900") (pin "57") (pinfunction "57_57") (pintype "passive"))
    )
    (net (code "100") (name "unconnected-(CN900-Pad58)") (class "Default")
      (node (ref "CN900") (pin "58") (pinfunction "58_58") (pintype "passive"))
    )
    (net (code "101") (name "unconnected-(CN900-Pad59)") (class "Default")
      (node (ref "CN900") (pin "59") (pinfunction "59_59") (pintype "passive"))
    )
    (net (code "102") (name "unconnected-(CN900-Pad60)") (class "Default")
      (node (ref "CN900") (pin "60") (pinfunction "60_60") (pintype "passive"))
    )
    (net (code "103") (name "unconnected-(CN900-Pad64)") (class "Default")
      (node (ref "CN900") (pin "64") (pinfunction "64_64") (pintype "passive"))
    )
    (net (code "104") (name "unconnected-(CN900-Pad66)") (class "Default")
      (node (ref "CN900") (pin "66") (pinfunction "66_66") (pintype "passive"))
    )
    (net (code "105") (name "unconnected-(CN900-Pad70)") (class "Default")
      (node (ref "CN900") (pin "70") (pinfunction "70_70") (pintype "passive"))
    )
    (net (code "106") (name "unconnected-(CN900-Pad72)") (class "Default")
      (node (ref "CN900") (pin "72") (pinfunction "72_72") (pintype "passive"))
    )
    (net (code "107") (name "unconnected-(CN900-Pad76)") (class "Default")
      (node (ref "CN900") (pin "76") (pinfunction "76_76") (pintype "passive"))
    )
    (net (code "108") (name "unconnected-(CN900-Pad78)") (class "Default")
      (node (ref "CN900") (pin "78") (pinfunction "78_78") (pintype "passive"))
    )
    (net (code "109") (name "unconnected-(CN900-Pad82)") (class "Default")
      (node (ref "CN900") (pin "82") (pinfunction "82_82") (pintype "passive"))
    )
    (net (code "110") (name "unconnected-(CN900-Pad84)") (class "Default")
      (node (ref "CN900") (pin "84") (pinfunction "84_84") (pintype "passive"))
    )
    (net (code "111") (name "unconnected-(CN900-Pad88)") (class "Default")
      (node (ref "CN900") (pin "88") (pinfunction "88_88") (pintype "passive"))
    )
    (net (code "112") (name "unconnected-(CN900-Pad90)") (class "Default")
      (node (ref "CN900") (pin "90") (pinfunction "90_90") (pintype "passive"))
    )
    (net (code "113") (name "unconnected-(CN900-Pad94)") (class "Default")
      (node (ref "CN900") (pin "94") (pinfunction "94_94") (pintype "passive"))
    )
    (net (code "114") (name "unconnected-(CN900-Pad96)") (class "Default")
      (node (ref "CN900") (pin "96") (pinfunction "96_96") (pintype "passive"))
    )
    (net (code "115") (name "unconnected-(CN900-Pad100)") (class "Default")
      (node (ref "CN900") (pin "100") (pinfunction "100_100") (pintype "passive"))
    )
    (net (code "116") (name "unconnected-(CN900-Pad102)") (class "Default")
      (node (ref "CN900") (pin "102") (pinfunction "102_102") (pintype "passive"))
    )
    (net (code "117") (name "unconnected-(CN900-Pad106)") (class "Default")
      (node (ref "CN900") (pin "106") (pinfunction "106_106") (pintype "passive"))
    )
    (net (code "118") (name "unconnected-(CN900-Pad131)") (class "Default")
      (node (ref "CN900") (pin "131") (pinfunction "131_131") (pintype "passive+no_connect"))
    )
    (net (code "119") (name "unconnected-(CN900-Pad132)") (class "Default")
      (node (ref "CN900") (pin "132") (pinfunction "132_132") (pintype "passive+no_connect"))
    )
    (net (code "120") (name "unconnected-(CN900-Pad143)") (class "Default")
      (node (ref "CN900") (pin "143") (pinfunction "143_143") (pintype "passive+no_connect"))
    )
    (net (code "121") (name "unconnected-(CN900-Pad144)") (class "Default")
      (node (ref "CN900") (pin "144") (pinfunction "144_144") (pintype "passive+no_connect"))
    )
    (net (code "122") (name "unconnected-(CN900-Pad155)") (class "Default")
      (node (ref "CN900") (pin "155") (pinfunction "155_155") (pintype "passive+no_connect"))
    )
    (net (code "123") (name "unconnected-(CN900-Pad156)") (class "Default")
      (node (ref "CN900") (pin "156") (pinfunction "156_156") (pintype "passive+no_connect"))
    )
    (net (code "124") (name "unconnected-(CN900-Pad185)") (class "Default")
      (node (ref "CN900") (pin "185") (pinfunction "185_185") (pintype "passive"))
    )
    (net (code "125") (name "unconnected-(CN900-Pad186)") (class "Default")
      (node (ref "CN900") (pin "186") (pinfunction "186_186") (pintype "passive"))
    )
    (net (code "126") (name "unconnected-(CN900-Pad187)") (class "Default")
      (node (ref "CN900") (pin "187") (pinfunction "187_187") (pintype "passive"))
    )
    (net (code "127") (name "unconnected-(CN900-Pad188)") (class "Default")
      (node (ref "CN900") (pin "188") (pinfunction "188_188") (pintype "passive"))
    )
    (net (code "128") (name "unconnected-(CN900-Pad191)") (class "Default")
      (node (ref "CN900") (pin "191") (pinfunction "191_191") (pintype "passive"))
    )
    (net (code "129") (name "unconnected-(CN900-Pad193)") (class "Default")
      (node (ref "CN900") (pin "193") (pinfunction "193_193") (pintype "passive"))
    )
    (net (code "130") (name "unconnected-(CN900-Pad197)") (class "Default")
      (node (ref "CN900") (pin "197") (pinfunction "197_197") (pintype "passive"))
    )
    (net (code "131") (name "unconnected-(CN900-Pad199)") (class "Default")
      (node (ref "CN900") (pin "199") (pinfunction "199_199") (pintype "passive"))
    )
    (net (code "132") (name "unconnected-(CN900-Pad221)") (class "Default")
      (node (ref "CN900") (pin "221") (pinfunction "221_221") (pintype "passive"))
    )
    (net (code "133") (name "unconnected-(CN900-Pad223)") (class "Default")
      (node (ref "CN900") (pin "223") (pinfunction "223_223") (pintype "passive"))
    )
    (net (code "134") (name "unconnected-(CN900-Pad239)") (class "Default")
      (node (ref "CN900") (pin "239") (pinfunction "239_239") (pintype "passive+no_connect"))
    )
    (net (code "135") (name "unconnected-(CN900-Pad240)") (class "Default")
      (node (ref "CN900") (pin "240") (pinfunction "240_240") (pintype "passive+no_connect"))
    )
    (net (code "136") (name "unconnected-(CN900-Pad251)") (class "Default")
      (node (ref "CN900") (pin "251") (pinfunction "251_251") (pintype "passive+no_connect"))
    )
    (net (code "137") (name "unconnected-(CN900-Pad252)") (class "Default")
      (node (ref "CN900") (pin "252") (pinfunction "252_252") (pintype "passive+no_connect"))
    )
  )
)
